# PWR_LDOs.net
KiCad netlist of a schematic drawn in Altium Designer
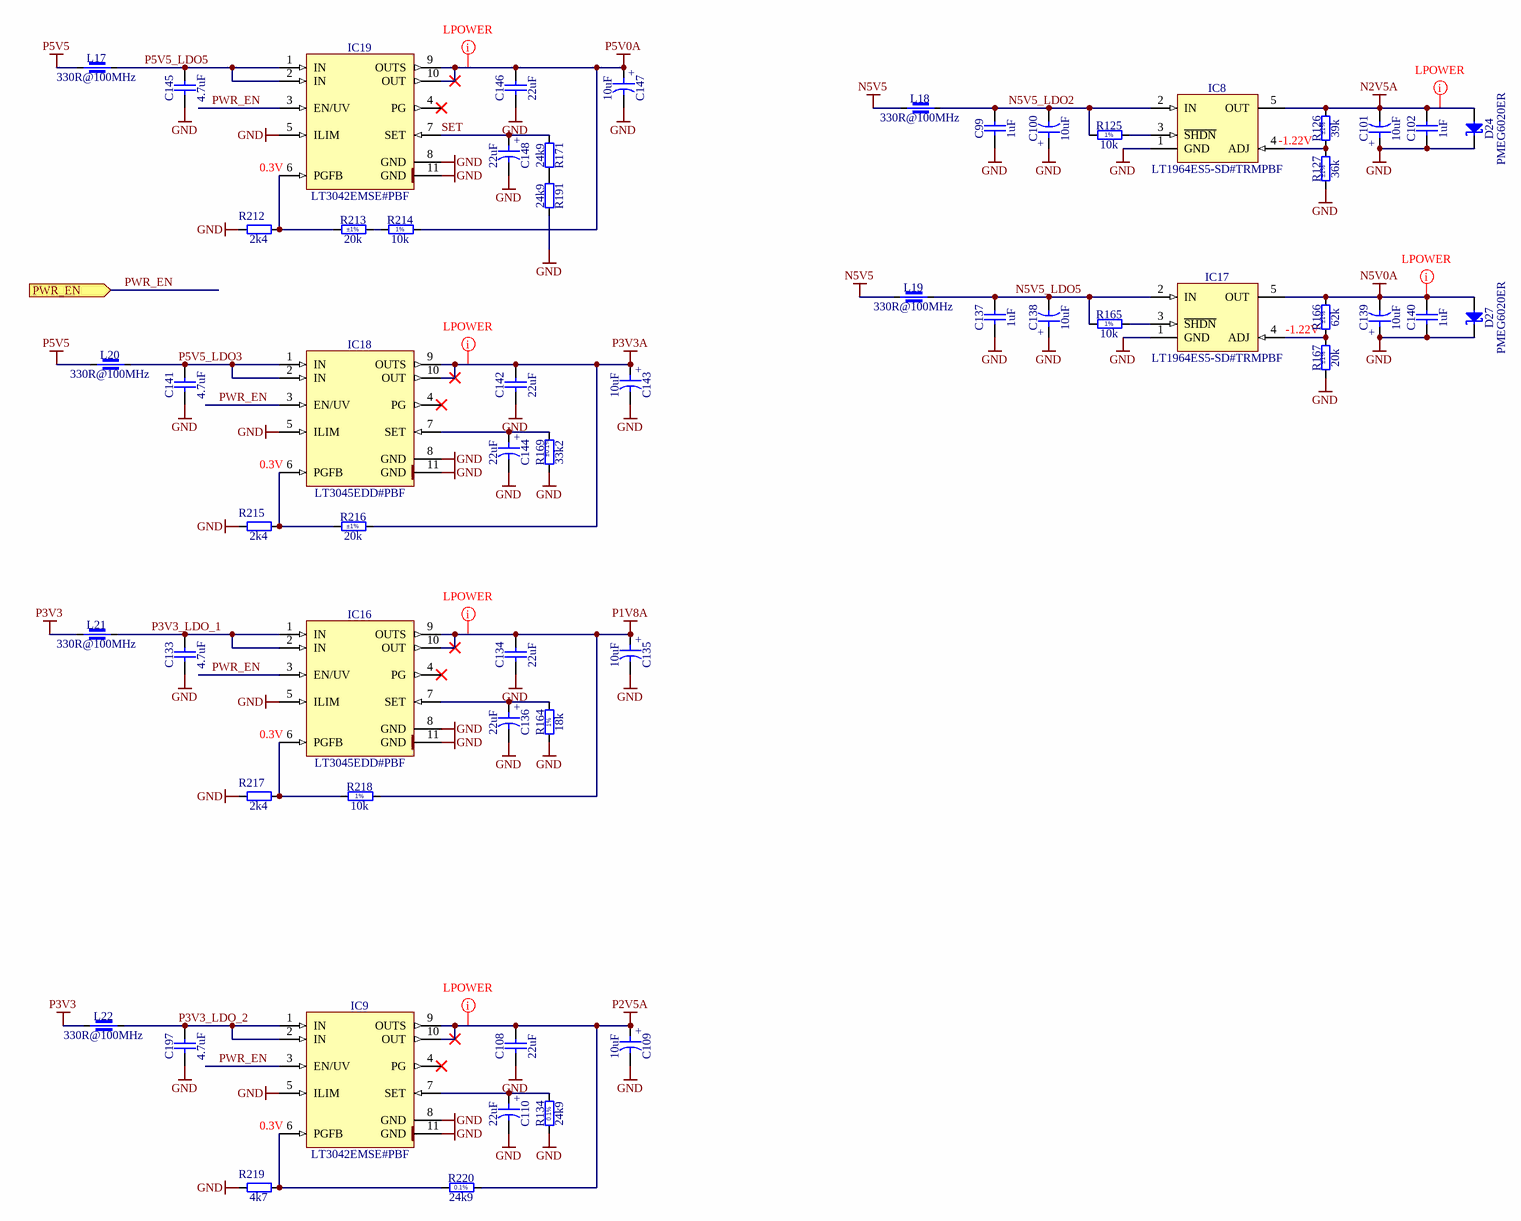
[diagram p0: PWR_LDOs.SchDoc]

(export (version "E")
  (design (tool "Eeschema 10.0.6"))
  (components
    (comp (ref "C99")
      (value "1uF")
      (footprint "CAPC1005X55N")
      (description "Non-polarised capacitor")
      (fields
        (field (name "PART NUMBER") "CC0402_1UF_16V_10%_X5R")
        (field (name "VOLTAGE") "16V")
        (field (name "AUTHOR") "CERN DEM JLC")
      )
      (libsource (lib "Capacitors") (part "Capacitor - non polarized"))
    )
    (comp (ref "C100")
      (value "10uF")
      (footprint "CAPMP3216X180N")
      (description "Polarised capacitor")
      (fields
        (field (name "PART NUMBER") "CTE3216-18_10UF_16V_20%_AVX_TCJ")
        (field (name "VOLTAGE") "16V")
        (field (name "AUTHOR") "CERN DEM JLC")
      )
      (libsource (lib "Capacitors") (part "Capacitor - polarized"))
    )
    (comp (ref "C101")
      (value "10uF")
      (footprint "CAPMP3216X180N")
      (description "Polarised capacitor")
      (fields
        (field (name "PART NUMBER") "CTE3216-18_10UF_16V_20%_AVX_TCJ")
        (field (name "VOLTAGE") "16V")
        (field (name "AUTHOR") "CERN DEM JLC")
      )
      (libsource (lib "Capacitors") (part "Capacitor - polarized"))
    )
    (comp (ref "C102")
      (value "1uF")
      (footprint "CAPC1005X55N")
      (description "Non-polarised capacitor")
      (fields
        (field (name "PART NUMBER") "CC0402_1UF_16V_10%_X5R")
        (field (name "VOLTAGE") "16V")
        (field (name "AUTHOR") "CERN DEM JLC")
      )
      (libsource (lib "Capacitors") (part "Capacitor - non polarized"))
    )
    (comp (ref "C108")
      (value "22uF")
      (footprint "CAPC2012X135N")
      (description "Non-polarised capacitor")
      (fields
        (field (name "PART NUMBER") "CC0805_22UF_16V_10%_X5R")
        (field (name "VOLTAGE") "16V")
        (field (name "AUTHOR") "CERN DEM JLC")
      )
      (libsource (lib "Capacitors") (part "Capacitor - non polarized"))
    )
    (comp (ref "C109")
      (value "10uF")
      (footprint "CAPMP3216X180N")
      (description "Polarised capacitor")
      (fields
        (field (name "PART NUMBER") "CTE3216-18_10UF_16V_20%_AVX_TCJ")
        (field (name "VOLTAGE") "16V")
        (field (name "AUTHOR") "CERN DEM JLC")
      )
      (libsource (lib "Capacitors") (part "Capacitor - polarized"))
    )
    (comp (ref "C110")
      (value "22uF")
      (footprint "CAPMP3216X180N")
      (description "Polarised capacitor")
      (fields
        (field (name "PART NUMBER") "CTE3216-18_22UF_10V_10%")
        (field (name "VOLTAGE") "10V")
        (field (name "AUTHOR") "CERN DEM JLC")
      )
      (libsource (lib "Capacitors") (part "Capacitor - polarized"))
    )
    (comp (ref "C133")
      (value "4.7uF")
      (footprint "CAPC1709X95N")
      (description "Non-polarised capacitor")
      (fields
        (field (name "PART NUMBER") "CC0603_4.7UF_16V_10%_X5R")
        (field (name "VOLTAGE") "16V")
        (field (name "AUTHOR") "CERN DEM JLC")
      )
      (libsource (lib "Capacitors") (part "Capacitor - non polarized"))
    )
    (comp (ref "C134")
      (value "22uF")
      (footprint "CAPC2012X135N")
      (description "Non-polarised capacitor")
      (fields
        (field (name "PART NUMBER") "CC0805_22UF_16V_10%_X5R")
        (field (name "VOLTAGE") "16V")
        (field (name "AUTHOR") "CERN DEM JLC")
      )
      (libsource (lib "Capacitors") (part "Capacitor - non polarized"))
    )
    (comp (ref "C135")
      (value "10uF")
      (footprint "CAPMP3216X180N")
      (description "Polarised capacitor")
      (fields
        (field (name "PART NUMBER") "CTE3216-18_10UF_16V_20%_AVX_TCJ")
        (field (name "VOLTAGE") "16V")
        (field (name "AUTHOR") "CERN DEM JLC")
      )
      (libsource (lib "Capacitors") (part "Capacitor - polarized"))
    )
    (comp (ref "C136")
      (value "22uF")
      (footprint "CAPMP3216X180N")
      (description "Polarised capacitor")
      (fields
        (field (name "PART NUMBER") "CTE3216-18_22UF_10V_10%")
        (field (name "VOLTAGE") "10V")
        (field (name "AUTHOR") "CERN DEM JLC")
      )
      (libsource (lib "Capacitors") (part "Capacitor - polarized"))
    )
    (comp (ref "C137")
      (value "1uF")
      (footprint "CAPC1005X55N")
      (description "Non-polarised capacitor")
      (fields
        (field (name "PART NUMBER") "CC0402_1UF_16V_10%_X5R")
        (field (name "VOLTAGE") "16V")
        (field (name "AUTHOR") "CERN DEM JLC")
      )
      (libsource (lib "Capacitors") (part "Capacitor - non polarized"))
    )
    (comp (ref "C138")
      (value "10uF")
      (footprint "CAPMP3216X180N")
      (description "Polarised capacitor")
      (fields
        (field (name "PART NUMBER") "CTE3216-18_10UF_16V_20%_AVX_TCJ")
        (field (name "VOLTAGE") "16V")
        (field (name "AUTHOR") "CERN DEM JLC")
      )
      (libsource (lib "Capacitors") (part "Capacitor - polarized"))
    )
    (comp (ref "C139")
      (value "10uF")
      (footprint "CAPMP3216X180N")
      (description "Polarised capacitor")
      (fields
        (field (name "PART NUMBER") "CTE3216-18_10UF_16V_20%_AVX_TCJ")
        (field (name "VOLTAGE") "16V")
        (field (name "AUTHOR") "CERN DEM JLC")
      )
      (libsource (lib "Capacitors") (part "Capacitor - polarized"))
    )
    (comp (ref "C140")
      (value "1uF")
      (footprint "CAPC1005X55N")
      (description "Non-polarised capacitor")
      (fields
        (field (name "PART NUMBER") "CC0402_1UF_16V_10%_X5R")
        (field (name "VOLTAGE") "16V")
        (field (name "AUTHOR") "CERN DEM JLC")
      )
      (libsource (lib "Capacitors") (part "Capacitor - non polarized"))
    )
    (comp (ref "C141")
      (value "4.7uF")
      (footprint "CAPC1709X95N")
      (description "Non-polarised capacitor")
      (fields
        (field (name "PART NUMBER") "CC0603_4.7UF_16V_10%_X5R")
        (field (name "VOLTAGE") "16V")
        (field (name "AUTHOR") "CERN DEM JLC")
      )
      (libsource (lib "Capacitors") (part "Capacitor - non polarized"))
    )
    (comp (ref "C142")
      (value "22uF")
      (footprint "CAPC2012X135N")
      (description "Non-polarised capacitor")
      (fields
        (field (name "PART NUMBER") "CC0805_22UF_16V_10%_X5R")
        (field (name "VOLTAGE") "16V")
        (field (name "AUTHOR") "CERN DEM JLC")
      )
      (libsource (lib "Capacitors") (part "Capacitor - non polarized"))
    )
    (comp (ref "C143")
      (value "10uF")
      (footprint "CAPMP3216X180N")
      (description "Polarised capacitor")
      (fields
        (field (name "PART NUMBER") "CTE3216-18_10UF_16V_20%_AVX_TCJ")
        (field (name "VOLTAGE") "16V")
        (field (name "AUTHOR") "CERN DEM JLC")
      )
      (libsource (lib "Capacitors") (part "Capacitor - polarized"))
    )
    (comp (ref "C144")
      (value "22uF")
      (footprint "CAPMP3216X180N")
      (description "Polarised capacitor")
      (fields
        (field (name "PART NUMBER") "CTE3216-18_22UF_10V_10%")
        (field (name "VOLTAGE") "10V")
        (field (name "AUTHOR") "CERN DEM JLC")
      )
      (libsource (lib "Capacitors") (part "Capacitor - polarized"))
    )
    (comp (ref "C145")
      (value "4.7uF")
      (footprint "CAPC1709X95N")
      (description "Non-polarised capacitor")
      (fields
        (field (name "PART NUMBER") "CC0603_4.7UF_16V_10%_X5R")
        (field (name "VOLTAGE") "16V")
        (field (name "AUTHOR") "CERN DEM JLC")
      )
      (libsource (lib "Capacitors") (part "Capacitor - non polarized"))
    )
    (comp (ref "C146")
      (value "22uF")
      (footprint "CAPC2012X135N")
      (description "Non-polarised capacitor")
      (fields
        (field (name "PART NUMBER") "CC0805_22UF_16V_10%_X5R")
        (field (name "VOLTAGE") "16V")
        (field (name "AUTHOR") "CERN DEM JLC")
      )
      (libsource (lib "Capacitors") (part "Capacitor - non polarized"))
    )
    (comp (ref "C147")
      (value "10uF")
      (footprint "CAPMP3216X180N")
      (description "Polarised capacitor")
      (fields
        (field (name "PART NUMBER") "CTE3216-18_10UF_16V_20%_AVX_TCJ")
        (field (name "VOLTAGE") "16V")
        (field (name "AUTHOR") "CERN DEM JLC")
      )
      (libsource (lib "Capacitors") (part "Capacitor - polarized"))
    )
    (comp (ref "C148")
      (value "22uF")
      (footprint "CAPMP3216X180N")
      (description "Polarised capacitor")
      (fields
        (field (name "PART NUMBER") "CTE3216-18_22UF_10V_10%")
        (field (name "VOLTAGE") "10V")
        (field (name "AUTHOR") "CERN DEM JLC")
      )
      (libsource (lib "Capacitors") (part "Capacitor - polarized"))
    )
    (comp (ref "C197")
      (value "4.7uF")
      (footprint "CAPC1709X95N")
      (description "Non-polarised capacitor")
      (fields
        (field (name "PART NUMBER") "CC0603_4.7UF_16V_10%_X5R")
        (field (name "VOLTAGE") "16V")
        (field (name "AUTHOR") "CERN DEM JLC")
      )
      (libsource (lib "Capacitors") (part "Capacitor - non polarized"))
    )
    (comp (ref "D24")
      (value "PMEG6020ER")
      (footprint "SODFL3517X110N")
      (description "Schottky Diode")
      (fields
        (field (name "VOLTAGE") "60V")
        (field (name "POWER") "2A")
        (field (name "AUTHOR") "CERN DEM JMW")
      )
      (libsource (lib "ICs And Semiconductors") (part "Diode Schottky"))
    )
    (comp (ref "D27")
      (value "PMEG6020ER")
      (footprint "SODFL3517X110N")
      (description "Schottky Diode")
      (fields
        (field (name "VOLTAGE") "60V")
        (field (name "POWER") "2A")
        (field (name "AUTHOR") "CERN DEM JMW")
      )
      (libsource (lib "ICs And Semiconductors") (part "Diode Schottky"))
    )
    (comp (ref "IC8")
      (value "LT1964ES5-SD#TRMPBF")
      (footprint "SOT95P280X100-5N")
      (description "200mA, Low Noise, Low Dropout Negative Micropower Regulator")
      (fields (field (name "MANUFACTURER") "LINEAR TECHNOLOGY") (field (name "AUTHOR") "CERN DEM JLC"))
      (libsource (lib "ICs And Semiconductors") (part "LT1964-SD"))
    )
    (comp (ref "IC9")
      (value "LT3042EMSE#PBF")
      (footprint "SOP50P490X110-11N-R168X198")
      (description "20V, 200mA, Ultralow Noise, Ultrahigh PSRR RF Linear Regulator")
      (fields (field (name "MANUFACTURER") "LINEAR TECHNOLOGY") (field (name "AUTHOR") "CERN DEM MR"))
      (libsource (lib "ICs And Semiconductors") (part "LT3042"))
    )
    (comp (ref "IC16")
      (value "LT3045EDD#PBF")
      (footprint "SON50P300X300X80-11N-R175X248")
      (description "20V, 500mA, Ultralow Noise, Ultrahigh PSRR Linear Regulator")
      (fields (field (name "MANUFACTURER") "LINEAR TECHNOLOGY") (field (name "AUTHOR") "CERN DEM JLC"))
      (libsource (lib "ICs And Semiconductors") (part "LT3045EDD"))
    )
    (comp (ref "IC17")
      (value "LT1964ES5-SD#TRMPBF")
      (footprint "SOT95P280X100-5N")
      (description "200mA, Low Noise, Low Dropout Negative Micropower Regulator")
      (fields (field (name "MANUFACTURER") "LINEAR TECHNOLOGY") (field (name "AUTHOR") "CERN DEM JLC"))
      (libsource (lib "ICs And Semiconductors") (part "LT1964-SD"))
    )
    (comp (ref "IC18")
      (value "LT3045EDD#PBF")
      (footprint "SON50P300X300X80-11N-R175X248")
      (description "20V, 500mA, Ultralow Noise, Ultrahigh PSRR Linear Regulator")
      (fields (field (name "MANUFACTURER") "LINEAR TECHNOLOGY") (field (name "AUTHOR") "CERN DEM JLC"))
      (libsource (lib "ICs And Semiconductors") (part "LT3045EDD"))
    )
    (comp (ref "IC19")
      (value "LT3042EMSE#PBF")
      (footprint "SOP50P490X110-11N-R168X198")
      (description "20V, 200mA, Ultralow Noise, Ultrahigh PSRR RF Linear Regulator")
      (fields (field (name "MANUFACTURER") "LINEAR TECHNOLOGY") (field (name "AUTHOR") "CERN DEM MR"))
      (libsource (lib "ICs And Semiconductors") (part "LT3042"))
    )
    (comp (ref "L17")
      (value "330R@100MHz")
      (footprint "INDC1608X75N")
      (fields
        (field (name "PART NUMBER") "IND0603_TDK_MPZ1608S331ATD25")
        (field (name "POWER") "1.7A")
        (field (name "TOLERANCE") "±25%")
        (field (name "AUTHOR") "CERN DEM JLC")
      )
      (libsource (lib "Inductors & Transformers") (part "Ferrite Bead"))
    )
    (comp (ref "L18")
      (value "330R@100MHz")
      (footprint "INDC1608X75N")
      (fields
        (field (name "PART NUMBER") "IND0603_TDK_MPZ1608S331ATD25")
        (field (name "POWER") "1.7A")
        (field (name "TOLERANCE") "±25%")
        (field (name "AUTHOR") "CERN DEM JLC")
      )
      (libsource (lib "Inductors & Transformers") (part "Ferrite Bead"))
    )
    (comp (ref "L19")
      (value "330R@100MHz")
      (footprint "INDC1608X75N")
      (fields
        (field (name "PART NUMBER") "IND0603_TDK_MPZ1608S331ATD25")
        (field (name "POWER") "1.7A")
        (field (name "TOLERANCE") "±25%")
        (field (name "AUTHOR") "CERN DEM JLC")
      )
      (libsource (lib "Inductors & Transformers") (part "Ferrite Bead"))
    )
    (comp (ref "L20")
      (value "330R@100MHz")
      (footprint "INDC1608X75N")
      (fields
        (field (name "PART NUMBER") "IND0603_TDK_MPZ1608S331ATD25")
        (field (name "POWER") "1.7A")
        (field (name "TOLERANCE") "±25%")
        (field (name "AUTHOR") "CERN DEM JLC")
      )
      (libsource (lib "Inductors & Transformers") (part "Ferrite Bead"))
    )
    (comp (ref "L21")
      (value "330R@100MHz")
      (footprint "INDC1608X75N")
      (fields
        (field (name "PART NUMBER") "IND0603_TDK_MPZ1608S331ATD25")
        (field (name "POWER") "1.7A")
        (field (name "TOLERANCE") "±25%")
        (field (name "AUTHOR") "CERN DEM JLC")
      )
      (libsource (lib "Inductors & Transformers") (part "Ferrite Bead"))
    )
    (comp (ref "L22")
      (value "330R@100MHz")
      (footprint "INDC1608X75N")
      (fields
        (field (name "PART NUMBER") "IND0603_TDK_MPZ1608S331ATD25")
        (field (name "POWER") "1.7A")
        (field (name "TOLERANCE") "±25%")
        (field (name "AUTHOR") "CERN DEM JLC")
      )
      (libsource (lib "Inductors & Transformers") (part "Ferrite Bead"))
    )
    (comp (ref "R125")
      (value "10k")
      (footprint "RESC1005X40N")
      (description "Resistor - 1%")
      (fields
        (field (name "PART NUMBER") "R0402_10K_1%_0.0625W_100PPM")
        (field (name "MANUFACTURER") "GENERIC")
        (field (name "AUTHOR") "CERN DEM JLC")
      )
      (libsource (lib "Resistors") (part "Resistor - 1%"))
    )
    (comp (ref "R126")
      (value "39k")
      (footprint "RESC1005X40N")
      (description "Resistor - 1%")
      (fields
        (field (name "PART NUMBER") "R0402_39K_1%_0.0625W_100PPM")
        (field (name "POWER") "0.0625W")
        (field (name "TOLERANCE") "±1%")
        (field (name "AUTHOR") "CERN DEM JLC")
      )
      (libsource (lib "Resistors") (part "Resistor - 1%"))
    )
    (comp (ref "R127")
      (value "36k")
      (footprint "RESC1005X40N")
      (description "Resistor - 1%")
      (fields
        (field (name "PART NUMBER") "R0402_36K_1%_0.0625W_100PPM")
        (field (name "POWER") "0.0625W")
        (field (name "TOLERANCE") "±1%")
        (field (name "AUTHOR") "CERN DEM JLC")
      )
      (libsource (lib "Resistors") (part "Resistor - 1%"))
    )
    (comp (ref "R134")
      (value "24k9")
      (footprint "RESC1608X55N")
      (description "Resistor - 0.1%")
      (fields
        (field (name "PART NUMBER") "R0603_24K9_0.1%_0.063W_10PPM")
        (field (name "POWER") "0.063W")
        (field (name "AUTHOR") "CERN DEM JLC")
      )
      (libsource (lib "Resistors") (part "Resistor - 0.1%"))
    )
    (comp (ref "R164")
      (value "18k")
      (footprint "RESC1608X55N")
      (description "Resistor - 1%")
      (fields
        (field (name "PART NUMBER") "R0603_18K_1%_0.1W_100PPM")
        (field (name "POWER") "0.1W")
        (field (name "AUTHOR") "CERN DEM JLC")
      )
      (libsource (lib "Resistors") (part "Resistor - 1%"))
    )
    (comp (ref "R165")
      (value "10k")
      (footprint "RESC1005X40N")
      (description "Resistor - 1%")
      (fields
        (field (name "PART NUMBER") "R0402_10K_1%_0.0625W_100PPM")
        (field (name "MANUFACTURER") "GENERIC")
        (field (name "AUTHOR") "CERN DEM JLC")
      )
      (libsource (lib "Resistors") (part "Resistor - 1%"))
    )
    (comp (ref "R166")
      (value "62k")
      (footprint "RESC1005X40N")
      (description "Resistor - 1%")
      (fields
        (field (name "PART NUMBER") "R0402_62K_1%_0.0625W_100PPM")
        (field (name "POWER") "0.0625W")
        (field (name "TOLERANCE") "±1%")
        (field (name "AUTHOR") "CERN DEM JLC")
      )
      (libsource (lib "Resistors") (part "Resistor - 1%"))
    )
    (comp (ref "R167")
      (value "20k")
      (footprint "RESC1005X40N")
      (description "Resistor - 1%")
      (fields
        (field (name "PART NUMBER") "R0402_20K_1%_0.0625W_100PPM")
        (field (name "POWER") "0.0625W")
        (field (name "TOLERANCE") "±1%")
        (field (name "AUTHOR") "CERN DEM JLC")
      )
      (libsource (lib "Resistors") (part "Resistor - 1%"))
    )
    (comp (ref "R169")
      (value "33k2")
      (footprint "RESC1608X55N")
      (description "Resistor - 0.1%")
      (fields
        (field (name "PART NUMBER") "R0603_33K2_0.1%_0.063W_10PPM")
        (field (name "POWER") "0.063W")
        (field (name "TOLERANCE") "±0.1%")
        (field (name "AUTHOR") "CERN DEM JLC")
      )
      (libsource (lib "Resistors") (part "Resistor - 0.1%"))
    )
    (comp (ref "R171")
      (value "24k9")
      (footprint "RESC1608X55N")
      (description "Resistor - 0.1%")
      (fields
        (field (name "PART NUMBER") "R0603_24K9_0.1%_0.063W_10PPM")
        (field (name "MANUFACTURER") "GENERIC")
        (field (name "AUTHOR") "CERN DEM JLC")
      )
      (libsource (lib "Resistors") (part "Resistor - 0.1%"))
    )
    (comp (ref "R191")
      (value "24k9")
      (footprint "RESC1608X55N")
      (description "Resistor - 0.1%")
      (fields
        (field (name "PART NUMBER") "R0603_24K9_0.1%_0.063W_10PPM")
        (field (name "POWER") "0.063W")
        (field (name "AUTHOR") "CERN DEM JLC")
      )
      (libsource (lib "Resistors") (part "Resistor - 0.1%"))
    )
    (comp (ref "R212")
      (value "2k4")
      (footprint "RESC1005X40N")
      (description "Resistor - 1%")
      (fields
        (field (name "PART NUMBER") "R0402_2K4_1%_0.0625W_100PPM")
        (field (name "POWER") "0.0625W")
        (field (name "AUTHOR") "CERN DEM JLC")
      )
      (libsource (lib "Resistors") (part "Resistor - 1%"))
    )
    (comp (ref "R213")
      (value "20k")
      (footprint "RESC1005X40N")
      (description "Resistor - 1%")
      (fields
        (field (name "TOLERANCE") "±1%")
        (field (name "PART NUMBER") "R0402_20K_1%_0.0625W_100PPM")
        (field (name "POWER") "0.0625W")
        (field (name "AUTHOR") "CERN DEM JLC")
      )
      (libsource (lib "Resistors") (part "Resistor - 1%"))
    )
    (comp (ref "R214")
      (value "10k")
      (footprint "RESC1005X40N")
      (description "Resistor - 1%")
      (fields
        (field (name "PART NUMBER") "R0402_10K_1%_0.0625W_100PPM")
        (field (name "POWER") "0.0625W")
        (field (name "AUTHOR") "CERN DEM JLC")
      )
      (libsource (lib "Resistors") (part "Resistor - 1%"))
    )
    (comp (ref "R215")
      (value "2k4")
      (footprint "RESC1005X40N")
      (description "Resistor - 1%")
      (fields
        (field (name "PART NUMBER") "R0402_2K4_1%_0.0625W_100PPM")
        (field (name "POWER") "0.0625W")
        (field (name "AUTHOR") "CERN DEM JLC")
      )
      (libsource (lib "Resistors") (part "Resistor - 1%"))
    )
    (comp (ref "R216")
      (value "20k")
      (footprint "RESC1005X40N")
      (description "Resistor - 1%")
      (fields
        (field (name "TOLERANCE") "±1%")
        (field (name "PART NUMBER") "R0402_20K_1%_0.0625W_100PPM")
        (field (name "POWER") "0.0625W")
        (field (name "AUTHOR") "CERN DEM JLC")
      )
      (libsource (lib "Resistors") (part "Resistor - 1%"))
    )
    (comp (ref "R217")
      (value "2k4")
      (footprint "RESC1005X40N")
      (description "Resistor - 1%")
      (fields
        (field (name "PART NUMBER") "R0402_2K4_1%_0.0625W_100PPM")
        (field (name "POWER") "0.0625W")
        (field (name "AUTHOR") "CERN DEM JLC")
      )
      (libsource (lib "Resistors") (part "Resistor - 1%"))
    )
    (comp (ref "R218")
      (value "10k")
      (footprint "RESC1005X40N")
      (description "Resistor - 1%")
      (fields
        (field (name "PART NUMBER") "R0402_10K_1%_0.0625W_100PPM")
        (field (name "POWER") "0.0625W")
        (field (name "AUTHOR") "CERN DEM JLC")
      )
      (libsource (lib "Resistors") (part "Resistor - 1%"))
    )
    (comp (ref "R219")
      (value "4k7")
      (footprint "RESC1005X40N")
      (description "Resistor - 1%")
      (fields
        (field (name "PART NUMBER") "R0402_4K7_1%_0.0625W_100PPM")
        (field (name "POWER") "0.0625W")
        (field (name "AUTHOR") "CERN DEM JLC")
      )
      (libsource (lib "Resistors") (part "Resistor - 1%"))
    )
    (comp (ref "R220")
      (value "24k9")
      (footprint "RESC1608X55N")
      (description "Resistor - 0.1%")
      (fields
        (field (name "PART NUMBER") "R0603_24K9_0.1%_0.063W_10PPM")
        (field (name "POWER") "0.063W")
        (field (name "AUTHOR") "CERN DEM JLC")
      )
      (libsource (lib "Resistors") (part "Resistor - 0.1%"))
    )
  )
  (nets
    (net (code "1") (name "/N5V5_LDO2") (class "Default")
      (node (ref "C100") (pin "2") (pinfunction "2_2") (pintype "passive"))
      (node (ref "C99") (pin "2") (pinfunction "2_2") (pintype "passive"))
      (node (ref "IC8") (pin "2") (pinfunction "IN_2") (pintype "input"))
      (node (ref "L18") (pin "2") (pinfunction "2_2") (pintype "passive"))
      (node (ref "R125") (pin "1") (pinfunction "1_1") (pintype "passive"))
    )
    (net (code "2") (name "/N5V5_LDO5") (class "Default")
      (node (ref "C137") (pin "2") (pinfunction "2_2") (pintype "passive"))
      (node (ref "C138") (pin "2") (pinfunction "2_2") (pintype "passive"))
      (node (ref "IC17") (pin "2") (pinfunction "IN_2") (pintype "input"))
      (node (ref "L19") (pin "2") (pinfunction "2_2") (pintype "passive"))
      (node (ref "R165") (pin "1") (pinfunction "1_1") (pintype "passive"))
    )
    (net (code "3") (name "/P3V3_LDO_1") (class "Default")
      (node (ref "C133") (pin "2") (pinfunction "2_2") (pintype "passive"))
      (node (ref "IC16") (pin "1") (pinfunction "IN_1") (pintype "input"))
      (node (ref "IC16") (pin "2") (pinfunction "IN_2") (pintype "input"))
      (node (ref "L21") (pin "2") (pinfunction "2_2") (pintype "passive"))
    )
    (net (code "4") (name "/P3V3_LDO_2") (class "Default")
      (node (ref "C197") (pin "2") (pinfunction "2_2") (pintype "passive"))
      (node (ref "IC9") (pin "1") (pinfunction "IN_1") (pintype "input"))
      (node (ref "IC9") (pin "2") (pinfunction "IN_2") (pintype "input"))
      (node (ref "L22") (pin "2") (pinfunction "2_2") (pintype "passive"))
    )
    (net (code "5") (name "/P5V5_LDO3") (class "Default")
      (node (ref "C141") (pin "2") (pinfunction "2_2") (pintype "passive"))
      (node (ref "IC18") (pin "1") (pinfunction "IN_1") (pintype "input"))
      (node (ref "IC18") (pin "2") (pinfunction "IN_2") (pintype "input"))
      (node (ref "L20") (pin "2") (pinfunction "2_2") (pintype "passive"))
    )
    (net (code "6") (name "/P5V5_LDO5") (class "Default")
      (node (ref "C145") (pin "2") (pinfunction "2_2") (pintype "passive"))
      (node (ref "IC19") (pin "1") (pinfunction "IN_1") (pintype "input"))
      (node (ref "IC19") (pin "2") (pinfunction "IN_2") (pintype "input"))
      (node (ref "L17") (pin "2") (pinfunction "2_2") (pintype "passive"))
    )
    (net (code "7") (name "/PWR_EN") (class "Default")
      (node (ref "IC16") (pin "3") (pinfunction "EN/UV_3") (pintype "input"))
      (node (ref "IC18") (pin "3") (pinfunction "EN/UV_3") (pintype "input"))
      (node (ref "IC19") (pin "3") (pinfunction "EN/UV_3") (pintype "input"))
      (node (ref "IC9") (pin "3") (pinfunction "EN/UV_3") (pintype "input"))
    )
    (net (code "8") (name "/SET") (class "Default")
      (node (ref "C148") (pin "1") (pinfunction "1_1") (pintype "passive"))
      (node (ref "IC19") (pin "7") (pinfunction "SET_7") (pintype "input"))
      (node (ref "R171") (pin "1") (pinfunction "1_1") (pintype "passive"))
    )
    (net (code "9") (name "GND") (class "Default")
      (node (ref "C100") (pin "1") (pinfunction "1_1") (pintype "passive"))
      (node (ref "C101") (pin "1") (pinfunction "1_1") (pintype "passive"))
      (node (ref "C102") (pin "1") (pinfunction "1_1") (pintype "passive"))
      (node (ref "C108") (pin "1") (pinfunction "1_1") (pintype "passive"))
      (node (ref "C109") (pin "2") (pinfunction "2_2") (pintype "passive"))
      (node (ref "C110") (pin "2") (pinfunction "2_2") (pintype "passive"))
      (node (ref "C133") (pin "1") (pinfunction "1_1") (pintype "passive"))
      (node (ref "C134") (pin "1") (pinfunction "1_1") (pintype "passive"))
      (node (ref "C135") (pin "2") (pinfunction "2_2") (pintype "passive"))
      (node (ref "C136") (pin "2") (pinfunction "2_2") (pintype "passive"))
      (node (ref "C137") (pin "1") (pinfunction "1_1") (pintype "passive"))
      (node (ref "C138") (pin "1") (pinfunction "1_1") (pintype "passive"))
      (node (ref "C139") (pin "1") (pinfunction "1_1") (pintype "passive"))
      (node (ref "C140") (pin "1") (pinfunction "1_1") (pintype "passive"))
      (node (ref "C141") (pin "1") (pinfunction "1_1") (pintype "passive"))
      (node (ref "C142") (pin "1") (pinfunction "1_1") (pintype "passive"))
      (node (ref "C143") (pin "2") (pinfunction "2_2") (pintype "passive"))
      (node (ref "C144") (pin "2") (pinfunction "2_2") (pintype "passive"))
      (node (ref "C145") (pin "1") (pinfunction "1_1") (pintype "passive"))
      (node (ref "C146") (pin "1") (pinfunction "1_1") (pintype "passive"))
      (node (ref "C147") (pin "2") (pinfunction "2_2") (pintype "passive"))
      (node (ref "C148") (pin "2") (pinfunction "2_2") (pintype "passive"))
      (node (ref "C197") (pin "1") (pinfunction "1_1") (pintype "passive"))
      (node (ref "C99") (pin "1") (pinfunction "1_1") (pintype "passive"))
      (node (ref "D24") (pin "1") (pinfunction "C_1") (pintype "passive"))
      (node (ref "D27") (pin "1") (pinfunction "C_1") (pintype "passive"))
      (node (ref "IC16") (pin "11") (pinfunction "GND_11") (pintype "power_in"))
      (node (ref "IC16") (pin "5") (pinfunction "ILIM_5") (pintype "input"))
      (node (ref "IC16") (pin "8") (pinfunction "GND_8") (pintype "power_in"))
      (node (ref "IC17") (pin "1") (pinfunction "GND_1") (pintype "power_in"))
      (node (ref "IC18") (pin "11") (pinfunction "GND_11") (pintype "power_in"))
      (node (ref "IC18") (pin "5") (pinfunction "ILIM_5") (pintype "input"))
      (node (ref "IC18") (pin "8") (pinfunction "GND_8") (pintype "power_in"))
      (node (ref "IC19") (pin "11") (pinfunction "GND_11") (pintype "power_in"))
      (node (ref "IC19") (pin "5") (pinfunction "ILIM_5") (pintype "input"))
      (node (ref "IC19") (pin "8") (pinfunction "GND_8") (pintype "power_in"))
      (node (ref "IC8") (pin "1") (pinfunction "GND_1") (pintype "power_in"))
      (node (ref "IC9") (pin "11") (pinfunction "GND_11") (pintype "power_in"))
      (node (ref "IC9") (pin "5") (pinfunction "ILIM_5") (pintype "input"))
      (node (ref "IC9") (pin "8") (pinfunction "GND_8") (pintype "power_in"))
      (node (ref "R127") (pin "1") (pinfunction "1_1") (pintype "passive"))
      (node (ref "R134") (pin "1") (pinfunction "1_1") (pintype "passive"))
      (node (ref "R164") (pin "1") (pinfunction "1_1") (pintype "passive"))
      (node (ref "R167") (pin "1") (pinfunction "1_1") (pintype "passive"))
      (node (ref "R169") (pin "1") (pinfunction "1_1") (pintype "passive"))
      (node (ref "R191") (pin "2") (pinfunction "2_2") (pintype "passive"))
      (node (ref "R212") (pin "1") (pinfunction "1_1") (pintype "passive"))
      (node (ref "R215") (pin "1") (pinfunction "1_1") (pintype "passive"))
      (node (ref "R217") (pin "1") (pinfunction "1_1") (pintype "passive"))
      (node (ref "R219") (pin "1") (pinfunction "1_1") (pintype "passive"))
    )
    (net (code "10") (name "N2V5A") (class "Default")
      (node (ref "C101") (pin "2") (pinfunction "2_2") (pintype "passive"))
      (node (ref "C102") (pin "2") (pinfunction "2_2") (pintype "passive"))
      (node (ref "D24") (pin "2") (pinfunction "A_2") (pintype "passive"))
      (node (ref "IC8") (pin "5") (pinfunction "OUT_5") (pintype "power_in"))
      (node (ref "R126") (pin "2") (pinfunction "2_2") (pintype "passive"))
    )
    (net (code "11") (name "N5V0A") (class "Default")
      (node (ref "C139") (pin "2") (pinfunction "2_2") (pintype "passive"))
      (node (ref "C140") (pin "2") (pinfunction "2_2") (pintype "passive"))
      (node (ref "D27") (pin "2") (pinfunction "A_2") (pintype "passive"))
      (node (ref "IC17") (pin "5") (pinfunction "OUT_5") (pintype "power_in"))
      (node (ref "R166") (pin "2") (pinfunction "2_2") (pintype "passive"))
    )
    (net (code "12") (name "N5V5") (class "Default")
      (node (ref "L18") (pin "1") (pinfunction "1_1") (pintype "passive"))
      (node (ref "L19") (pin "1") (pinfunction "1_1") (pintype "passive"))
    )
    (net (code "13") (name "Net-(IC8-ADJ)") (class "Default")
      (node (ref "IC8") (pin "4") (pinfunction "ADJ_4") (pintype "input"))
      (node (ref "R126") (pin "1") (pinfunction "1_1") (pintype "passive"))
      (node (ref "R127") (pin "2") (pinfunction "2_2") (pintype "passive"))
    )
    (net (code "14") (name "Net-(IC8-~{SHDN})") (class "Default")
      (node (ref "IC8") (pin "3") (pinfunction "~{SHDN}_3") (pintype "input"))
      (node (ref "R125") (pin "2") (pinfunction "2_2") (pintype "passive"))
    )
    (net (code "15") (name "Net-(IC9-PGFB)") (class "Default")
      (node (ref "IC9") (pin "6") (pinfunction "PGFB_6") (pintype "input"))
      (node (ref "R219") (pin "2") (pinfunction "2_2") (pintype "passive"))
      (node (ref "R220") (pin "1") (pinfunction "1_1") (pintype "passive"))
    )
    (net (code "16") (name "Net-(IC9-SET)") (class "Default")
      (node (ref "C110") (pin "1") (pinfunction "1_1") (pintype "passive"))
      (node (ref "IC9") (pin "7") (pinfunction "SET_7") (pintype "input"))
      (node (ref "R134") (pin "2") (pinfunction "2_2") (pintype "passive"))
    )
    (net (code "17") (name "Net-(IC16-PGFB)") (class "Default")
      (node (ref "IC16") (pin "6") (pinfunction "PGFB_6") (pintype "input"))
      (node (ref "R217") (pin "2") (pinfunction "2_2") (pintype "passive"))
      (node (ref "R218") (pin "1") (pinfunction "1_1") (pintype "passive"))
    )
    (net (code "18") (name "Net-(IC16-SET)") (class "Default")
      (node (ref "C136") (pin "1") (pinfunction "1_1") (pintype "passive"))
      (node (ref "IC16") (pin "7") (pinfunction "SET_7") (pintype "input"))
      (node (ref "R164") (pin "2") (pinfunction "2_2") (pintype "passive"))
    )
    (net (code "19") (name "Net-(IC17-ADJ)") (class "Default")
      (node (ref "IC17") (pin "4") (pinfunction "ADJ_4") (pintype "input"))
      (node (ref "R166") (pin "1") (pinfunction "1_1") (pintype "passive"))
      (node (ref "R167") (pin "2") (pinfunction "2_2") (pintype "passive"))
    )
    (net (code "20") (name "Net-(IC17-~{SHDN})") (class "Default")
      (node (ref "IC17") (pin "3") (pinfunction "~{SHDN}_3") (pintype "input"))
      (node (ref "R165") (pin "2") (pinfunction "2_2") (pintype "passive"))
    )
    (net (code "21") (name "Net-(IC18-PGFB)") (class "Default")
      (node (ref "IC18") (pin "6") (pinfunction "PGFB_6") (pintype "input"))
      (node (ref "R215") (pin "2") (pinfunction "2_2") (pintype "passive"))
      (node (ref "R216") (pin "1") (pinfunction "1_1") (pintype "passive"))
    )
    (net (code "22") (name "Net-(IC18-SET)") (class "Default")
      (node (ref "C144") (pin "1") (pinfunction "1_1") (pintype "passive"))
      (node (ref "IC18") (pin "7") (pinfunction "SET_7") (pintype "input"))
      (node (ref "R169") (pin "2") (pinfunction "2_2") (pintype "passive"))
    )
    (net (code "23") (name "Net-(IC19-PGFB)") (class "Default")
      (node (ref "IC19") (pin "6") (pinfunction "PGFB_6") (pintype "input"))
      (node (ref "R212") (pin "2") (pinfunction "2_2") (pintype "passive"))
      (node (ref "R213") (pin "1") (pinfunction "1_1") (pintype "passive"))
    )
    (net (code "24") (name "Net-(R171-Pad2)") (class "Default")
      (node (ref "R171") (pin "2") (pinfunction "2_2") (pintype "passive"))
      (node (ref "R191") (pin "1") (pinfunction "1_1") (pintype "passive"))
    )
    (net (code "25") (name "Net-(R213-Pad2)") (class "Default")
      (node (ref "R213") (pin "2") (pinfunction "2_2") (pintype "passive"))
      (node (ref "R214") (pin "1") (pinfunction "1_1") (pintype "passive"))
    )
    (net (code "26") (name "P1V8A") (class "Default")
      (node (ref "C134") (pin "2") (pinfunction "2_2") (pintype "passive"))
      (node (ref "C135") (pin "1") (pinfunction "1_1") (pintype "passive"))
      (node (ref "IC16") (pin "10") (pinfunction "OUT_10") (pintype "output"))
      (node (ref "IC16") (pin "9") (pinfunction "OUTS_9") (pintype "output"))
      (node (ref "R218") (pin "2") (pinfunction "2_2") (pintype "passive"))
    )
    (net (code "27") (name "P2V5A") (class "Default")
      (node (ref "C108") (pin "2") (pinfunction "2_2") (pintype "passive"))
      (node (ref "C109") (pin "1") (pinfunction "1_1") (pintype "passive"))
      (node (ref "IC9") (pin "10") (pinfunction "OUT_10") (pintype "output"))
      (node (ref "IC9") (pin "9") (pinfunction "OUTS_9") (pintype "output"))
      (node (ref "R220") (pin "2") (pinfunction "2_2") (pintype "passive"))
    )
    (net (code "28") (name "P3V3") (class "Default")
      (node (ref "L21") (pin "1") (pinfunction "1_1") (pintype "passive"))
      (node (ref "L22") (pin "1") (pinfunction "1_1") (pintype "passive"))
    )
    (net (code "29") (name "P3V3A") (class "Default")
      (node (ref "C142") (pin "2") (pinfunction "2_2") (pintype "passive"))
      (node (ref "C143") (pin "1") (pinfunction "1_1") (pintype "passive"))
      (node (ref "IC18") (pin "10") (pinfunction "OUT_10") (pintype "output"))
      (node (ref "IC18") (pin "9") (pinfunction "OUTS_9") (pintype "output"))
      (node (ref "R216") (pin "2") (pinfunction "2_2") (pintype "passive"))
    )
    (net (code "30") (name "P5V0A") (class "Default")
      (node (ref "C146") (pin "2") (pinfunction "2_2") (pintype "passive"))
      (node (ref "C147") (pin "1") (pinfunction "1_1") (pintype "passive"))
      (node (ref "IC19") (pin "10") (pinfunction "OUT_10") (pintype "output"))
      (node (ref "IC19") (pin "9") (pinfunction "OUTS_9") (pintype "output"))
      (node (ref "R214") (pin "2") (pinfunction "2_2") (pintype "passive"))
    )
    (net (code "31") (name "P5V5") (class "Default")
      (node (ref "L17") (pin "1") (pinfunction "1_1") (pintype "passive"))
      (node (ref "L20") (pin "1") (pinfunction "1_1") (pintype "passive"))
    )
    (net (code "32") (name "unconnected-(IC9-PG-Pad4)") (class "Default")
      (node (ref "IC9") (pin "4") (pinfunction "PG_4") (pintype "output+no_connect"))
    )
    (net (code "33") (name "unconnected-(IC16-PG-Pad4)") (class "Default")
      (node (ref "IC16") (pin "4") (pinfunction "PG_4") (pintype "output+no_connect"))
    )
    (net (code "34") (name "unconnected-(IC18-PG-Pad4)") (class "Default")
      (node (ref "IC18") (pin "4") (pinfunction "PG_4") (pintype "output+no_connect"))
    )
    (net (code "35") (name "unconnected-(IC19-PG-Pad4)") (class "Default")
      (node (ref "IC19") (pin "4") (pinfunction "PG_4") (pintype "output+no_connect"))
    )
  )
)
